# StraightThumbs.net
KiCad netlist of a schematic drawn in EAGLE
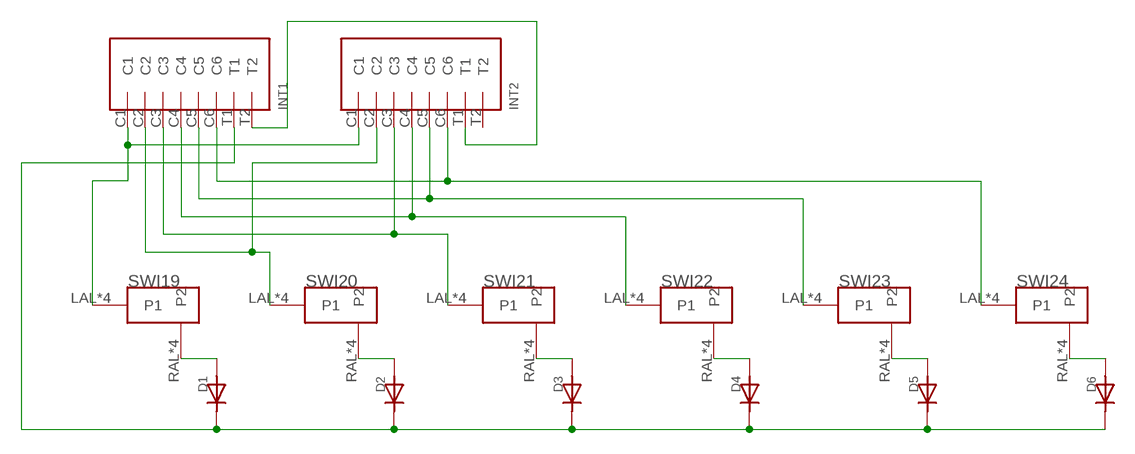
[diagram p0: schematic, sheet 1]

(export (version "E")
  (design (tool "Eeschema 10.0.6"))
  (components
    (comp (ref "D1")
      (value "DIODE")
      (footprint "eagle-import:DIODE_COMBO")
      (libsource (lib "eagle-import") (part "DIODE"))
    )
    (comp (ref "D2")
      (value "DIODE")
      (footprint "eagle-import:DIODE_COMBO")
      (libsource (lib "eagle-import") (part "DIODE"))
    )
    (comp (ref "D3")
      (value "DIODE")
      (footprint "eagle-import:DIODE_COMBO")
      (libsource (lib "eagle-import") (part "DIODE"))
    )
    (comp (ref "D4")
      (value "DIODE")
      (footprint "eagle-import:DIODE_COMBO")
      (libsource (lib "eagle-import") (part "DIODE"))
    )
    (comp (ref "D5")
      (value "DIODE")
      (footprint "eagle-import:DIODE_COMBO")
      (libsource (lib "eagle-import") (part "DIODE"))
    )
    (comp (ref "D6")
      (value "DIODE")
      (footprint "eagle-import:DIODE_COMBO")
      (libsource (lib "eagle-import") (part "DIODE"))
    )
    (comp (ref "INT1")
      (value "INTRCNNT")
      (footprint "eagle-import:INTRCNNT")
      (libsource (lib "eagle-import") (part "INTRCNNT"))
    )
    (comp (ref "INT2")
      (value "INTRCNNT")
      (footprint "eagle-import:INTRCNNT")
      (libsource (lib "eagle-import") (part "INTRCNNT"))
    )
    (comp (ref "SWI19")
      (value "MX/ALPSDOUBLESIDED")
      (footprint "eagle-import:DOUBLED_MX_ALPS")
      (libsource (lib "eagle-import") (part "MX/ALPSDOUBLESIDED"))
    )
    (comp (ref "SWI20")
      (value "MX/ALPSDOUBLESIDED")
      (footprint "eagle-import:DOUBLED_MX_ALPS")
      (libsource (lib "eagle-import") (part "MX/ALPSDOUBLESIDED"))
    )
    (comp (ref "SWI21")
      (value "MX/ALPSDOUBLESIDED")
      (footprint "eagle-import:DOUBLED_MX_ALPS")
      (libsource (lib "eagle-import") (part "MX/ALPSDOUBLESIDED"))
    )
    (comp (ref "SWI22")
      (value "MX/ALPSDOUBLESIDED")
      (footprint "eagle-import:DOUBLED_MX_ALPS")
      (libsource (lib "eagle-import") (part "MX/ALPSDOUBLESIDED"))
    )
    (comp (ref "SWI23")
      (value "MX/ALPSDOUBLESIDED")
      (footprint "eagle-import:DOUBLED_MX_ALPS")
      (libsource (lib "eagle-import") (part "MX/ALPSDOUBLESIDED"))
    )
    (comp (ref "SWI24")
      (value "MX/ALPSDOUBLESIDED")
      (footprint "eagle-import:DOUBLED_MX_ALPS")
      (libsource (lib "eagle-import") (part "MX/ALPSDOUBLESIDED"))
    )
  )
  (nets
    (net (code "1") (name "Net-(D1-AN-PadANOSB)") (class "Default")
      (node (ref "D1") (pin "ANOSB") (pinfunction "AN_ANOSB") (pintype "bidirectional"))
      (node (ref "D1") (pin "ANOST") (pinfunction "AN_ANOST") (pintype "bidirectional"))
      (node (ref "D1") (pin "ANOT") (pinfunction "AN_ANOT") (pintype "bidirectional"))
      (node (ref "SWI19") (pin "RAL") (pinfunction "P2_RAL") (pintype "bidirectional"))
      (node (ref "SWI19") (pin "RAR") (pinfunction "P2_RAR") (pintype "bidirectional"))
      (node (ref "SWI19") (pin "RCL") (pinfunction "P2_RCL") (pintype "bidirectional"))
      (node (ref "SWI19") (pin "RCR") (pinfunction "P2_RCR") (pintype "bidirectional"))
    )
    (net (code "2") (name "Net-(D1-CAT-PadCATSB)") (class "Default")
      (node (ref "D1") (pin "CATSB") (pinfunction "CAT_CATSB") (pintype "bidirectional"))
      (node (ref "D1") (pin "CATST") (pinfunction "CAT_CATST") (pintype "bidirectional"))
      (node (ref "D1") (pin "CATT") (pinfunction "CAT_CATT") (pintype "bidirectional"))
      (node (ref "D2") (pin "CATSB") (pinfunction "CAT_CATSB") (pintype "bidirectional"))
      (node (ref "D2") (pin "CATST") (pinfunction "CAT_CATST") (pintype "bidirectional"))
      (node (ref "D2") (pin "CATT") (pinfunction "CAT_CATT") (pintype "bidirectional"))
      (node (ref "D3") (pin "CATSB") (pinfunction "CAT_CATSB") (pintype "bidirectional"))
      (node (ref "D3") (pin "CATST") (pinfunction "CAT_CATST") (pintype "bidirectional"))
      (node (ref "D3") (pin "CATT") (pinfunction "CAT_CATT") (pintype "bidirectional"))
      (node (ref "D4") (pin "CATSB") (pinfunction "CAT_CATSB") (pintype "bidirectional"))
      (node (ref "D4") (pin "CATST") (pinfunction "CAT_CATST") (pintype "bidirectional"))
      (node (ref "D4") (pin "CATT") (pinfunction "CAT_CATT") (pintype "bidirectional"))
      (node (ref "D5") (pin "CATSB") (pinfunction "CAT_CATSB") (pintype "bidirectional"))
      (node (ref "D5") (pin "CATST") (pinfunction "CAT_CATST") (pintype "bidirectional"))
      (node (ref "D5") (pin "CATT") (pinfunction "CAT_CATT") (pintype "bidirectional"))
      (node (ref "D6") (pin "CATSB") (pinfunction "CAT_CATSB") (pintype "bidirectional"))
      (node (ref "D6") (pin "CATST") (pinfunction "CAT_CATST") (pintype "bidirectional"))
      (node (ref "D6") (pin "CATT") (pinfunction "CAT_CATT") (pintype "bidirectional"))
      (node (ref "INT1") (pin "T1") (pinfunction "T1_T1") (pintype "bidirectional"))
    )
    (net (code "3") (name "Net-(D2-AN-PadANOSB)") (class "Default")
      (node (ref "D2") (pin "ANOSB") (pinfunction "AN_ANOSB") (pintype "bidirectional"))
      (node (ref "D2") (pin "ANOST") (pinfunction "AN_ANOST") (pintype "bidirectional"))
      (node (ref "D2") (pin "ANOT") (pinfunction "AN_ANOT") (pintype "bidirectional"))
      (node (ref "SWI20") (pin "RAL") (pinfunction "P2_RAL") (pintype "bidirectional"))
      (node (ref "SWI20") (pin "RAR") (pinfunction "P2_RAR") (pintype "bidirectional"))
      (node (ref "SWI20") (pin "RCL") (pinfunction "P2_RCL") (pintype "bidirectional"))
      (node (ref "SWI20") (pin "RCR") (pinfunction "P2_RCR") (pintype "bidirectional"))
    )
    (net (code "4") (name "Net-(D3-AN-PadANOSB)") (class "Default")
      (node (ref "D3") (pin "ANOSB") (pinfunction "AN_ANOSB") (pintype "bidirectional"))
      (node (ref "D3") (pin "ANOST") (pinfunction "AN_ANOST") (pintype "bidirectional"))
      (node (ref "D3") (pin "ANOT") (pinfunction "AN_ANOT") (pintype "bidirectional"))
      (node (ref "SWI21") (pin "RAL") (pinfunction "P2_RAL") (pintype "bidirectional"))
      (node (ref "SWI21") (pin "RAR") (pinfunction "P2_RAR") (pintype "bidirectional"))
      (node (ref "SWI21") (pin "RCL") (pinfunction "P2_RCL") (pintype "bidirectional"))
      (node (ref "SWI21") (pin "RCR") (pinfunction "P2_RCR") (pintype "bidirectional"))
    )
    (net (code "5") (name "Net-(D4-AN-PadANOSB)") (class "Default")
      (node (ref "D4") (pin "ANOSB") (pinfunction "AN_ANOSB") (pintype "bidirectional"))
      (node (ref "D4") (pin "ANOST") (pinfunction "AN_ANOST") (pintype "bidirectional"))
      (node (ref "D4") (pin "ANOT") (pinfunction "AN_ANOT") (pintype "bidirectional"))
      (node (ref "SWI22") (pin "RAL") (pinfunction "P2_RAL") (pintype "bidirectional"))
      (node (ref "SWI22") (pin "RAR") (pinfunction "P2_RAR") (pintype "bidirectional"))
      (node (ref "SWI22") (pin "RCL") (pinfunction "P2_RCL") (pintype "bidirectional"))
      (node (ref "SWI22") (pin "RCR") (pinfunction "P2_RCR") (pintype "bidirectional"))
    )
    (net (code "6") (name "Net-(D5-AN-PadANOSB)") (class "Default")
      (node (ref "D5") (pin "ANOSB") (pinfunction "AN_ANOSB") (pintype "bidirectional"))
      (node (ref "D5") (pin "ANOST") (pinfunction "AN_ANOST") (pintype "bidirectional"))
      (node (ref "D5") (pin "ANOT") (pinfunction "AN_ANOT") (pintype "bidirectional"))
      (node (ref "SWI23") (pin "RAL") (pinfunction "P2_RAL") (pintype "bidirectional"))
      (node (ref "SWI23") (pin "RAR") (pinfunction "P2_RAR") (pintype "bidirectional"))
      (node (ref "SWI23") (pin "RCL") (pinfunction "P2_RCL") (pintype "bidirectional"))
      (node (ref "SWI23") (pin "RCR") (pinfunction "P2_RCR") (pintype "bidirectional"))
    )
    (net (code "7") (name "Net-(D6-AN-PadANOSB)") (class "Default")
      (node (ref "D6") (pin "ANOSB") (pinfunction "AN_ANOSB") (pintype "bidirectional"))
      (node (ref "D6") (pin "ANOST") (pinfunction "AN_ANOST") (pintype "bidirectional"))
      (node (ref "D6") (pin "ANOT") (pinfunction "AN_ANOT") (pintype "bidirectional"))
      (node (ref "SWI24") (pin "RAL") (pinfunction "P2_RAL") (pintype "bidirectional"))
      (node (ref "SWI24") (pin "RAR") (pinfunction "P2_RAR") (pintype "bidirectional"))
      (node (ref "SWI24") (pin "RCL") (pinfunction "P2_RCL") (pintype "bidirectional"))
      (node (ref "SWI24") (pin "RCR") (pinfunction "P2_RCR") (pintype "bidirectional"))
    )
    (net (code "8") (name "Net-(INT1-PadC1)") (class "Default")
      (node (ref "INT1") (pin "C1") (pinfunction "C1_C1") (pintype "bidirectional"))
      (node (ref "INT2") (pin "C1") (pinfunction "C1_C1") (pintype "bidirectional"))
      (node (ref "SWI19") (pin "LAL") (pinfunction "P1_LAL") (pintype "bidirectional"))
      (node (ref "SWI19") (pin "LAR") (pinfunction "P1_LAR") (pintype "bidirectional"))
      (node (ref "SWI19") (pin "LCL") (pinfunction "P1_LCL") (pintype "bidirectional"))
      (node (ref "SWI19") (pin "LCR") (pinfunction "P1_LCR") (pintype "bidirectional"))
    )
    (net (code "9") (name "Net-(INT1-PadC2)") (class "Default")
      (node (ref "INT1") (pin "C2") (pinfunction "C2_C2") (pintype "bidirectional"))
      (node (ref "INT2") (pin "C2") (pinfunction "C2_C2") (pintype "bidirectional"))
      (node (ref "SWI20") (pin "LAL") (pinfunction "P1_LAL") (pintype "bidirectional"))
      (node (ref "SWI20") (pin "LAR") (pinfunction "P1_LAR") (pintype "bidirectional"))
      (node (ref "SWI20") (pin "LCL") (pinfunction "P1_LCL") (pintype "bidirectional"))
      (node (ref "SWI20") (pin "LCR") (pinfunction "P1_LCR") (pintype "bidirectional"))
    )
    (net (code "10") (name "Net-(INT1-PadC3)") (class "Default")
      (node (ref "INT1") (pin "C3") (pinfunction "C3_C3") (pintype "bidirectional"))
      (node (ref "INT2") (pin "C3") (pinfunction "C3_C3") (pintype "bidirectional"))
      (node (ref "SWI21") (pin "LAL") (pinfunction "P1_LAL") (pintype "bidirectional"))
      (node (ref "SWI21") (pin "LAR") (pinfunction "P1_LAR") (pintype "bidirectional"))
      (node (ref "SWI21") (pin "LCL") (pinfunction "P1_LCL") (pintype "bidirectional"))
      (node (ref "SWI21") (pin "LCR") (pinfunction "P1_LCR") (pintype "bidirectional"))
    )
    (net (code "11") (name "Net-(INT1-PadC4)") (class "Default")
      (node (ref "INT1") (pin "C4") (pinfunction "C4_C4") (pintype "bidirectional"))
      (node (ref "INT2") (pin "C4") (pinfunction "C4_C4") (pintype "bidirectional"))
      (node (ref "SWI22") (pin "LAL") (pinfunction "P1_LAL") (pintype "bidirectional"))
      (node (ref "SWI22") (pin "LAR") (pinfunction "P1_LAR") (pintype "bidirectional"))
      (node (ref "SWI22") (pin "LCL") (pinfunction "P1_LCL") (pintype "bidirectional"))
      (node (ref "SWI22") (pin "LCR") (pinfunction "P1_LCR") (pintype "bidirectional"))
    )
    (net (code "12") (name "Net-(INT1-PadC5)") (class "Default")
      (node (ref "INT1") (pin "C5") (pinfunction "C5_C5") (pintype "bidirectional"))
      (node (ref "INT2") (pin "C5") (pinfunction "C5_C5") (pintype "bidirectional"))
      (node (ref "SWI23") (pin "LAL") (pinfunction "P1_LAL") (pintype "bidirectional"))
      (node (ref "SWI23") (pin "LAR") (pinfunction "P1_LAR") (pintype "bidirectional"))
      (node (ref "SWI23") (pin "LCL") (pinfunction "P1_LCL") (pintype "bidirectional"))
      (node (ref "SWI23") (pin "LCR") (pinfunction "P1_LCR") (pintype "bidirectional"))
    )
    (net (code "13") (name "Net-(INT1-PadC6)") (class "Default")
      (node (ref "INT1") (pin "C6") (pinfunction "C6_C6") (pintype "bidirectional"))
      (node (ref "INT2") (pin "C6") (pinfunction "C6_C6") (pintype "bidirectional"))
      (node (ref "SWI24") (pin "LAL") (pinfunction "P1_LAL") (pintype "bidirectional"))
      (node (ref "SWI24") (pin "LAR") (pinfunction "P1_LAR") (pintype "bidirectional"))
      (node (ref "SWI24") (pin "LCL") (pinfunction "P1_LCL") (pintype "bidirectional"))
      (node (ref "SWI24") (pin "LCR") (pinfunction "P1_LCR") (pintype "bidirectional"))
    )
    (net (code "14") (name "Net-(INT1-PadT2)") (class "Default")
      (node (ref "INT1") (pin "T2") (pinfunction "T2_T2") (pintype "bidirectional"))
      (node (ref "INT2") (pin "T1") (pinfunction "T1_T1") (pintype "bidirectional"))
    )
    (net (code "15") (name "unconnected-(INT2-PadT2)") (class "Default")
      (node (ref "INT2") (pin "T2") (pinfunction "T2_T2") (pintype "bidirectional"))
    )
  )
)
